# indication_panel.net
KiCad netlist of a schematic drawn in EAGLE
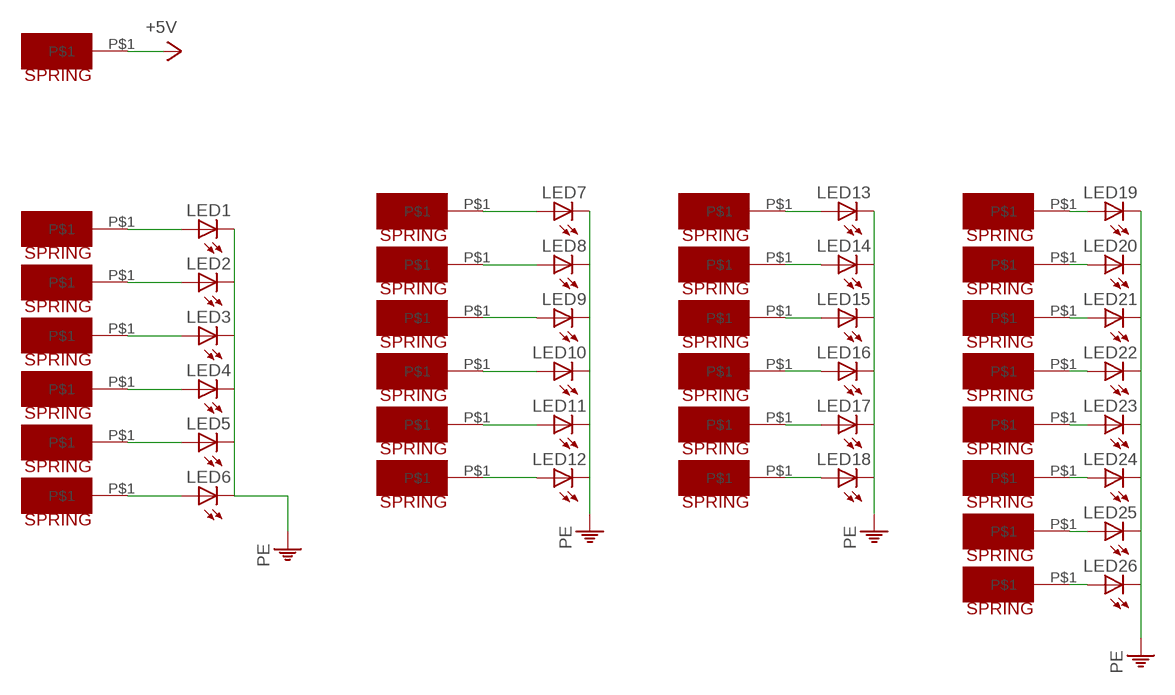
[diagram p0: schematic, sheet 1]

(export (version "E")
  (design (tool "Eeschema 10.0.6"))
  (components
    (comp (ref "+5V")
      (value "SPRING")
      (footprint "eagle-import:SPRING")
      (libsource (lib "eagle-import") (part "SPRING"))
    )
    (comp (ref "LED1")
      (value "LEDCHIPLED_0805")
      (footprint "eagle-import:CHIPLED_0805")
      (libsource (lib "eagle-import") (part "LEDCHIPLED_0805"))
    )
    (comp (ref "LED2")
      (value "LEDCHIPLED_0805")
      (footprint "eagle-import:CHIPLED_0805")
      (libsource (lib "eagle-import") (part "LEDCHIPLED_0805"))
    )
    (comp (ref "LED3")
      (value "LEDCHIPLED_0805")
      (footprint "eagle-import:CHIPLED_0805")
      (libsource (lib "eagle-import") (part "LEDCHIPLED_0805"))
    )
    (comp (ref "LED4")
      (value "LEDCHIPLED_0805")
      (footprint "eagle-import:CHIPLED_0805")
      (libsource (lib "eagle-import") (part "LEDCHIPLED_0805"))
    )
    (comp (ref "LED5")
      (value "LEDCHIPLED_0805")
      (footprint "eagle-import:CHIPLED_0805")
      (libsource (lib "eagle-import") (part "LEDCHIPLED_0805"))
    )
    (comp (ref "LED6")
      (value "LEDCHIPLED_0805")
      (footprint "eagle-import:CHIPLED_0805")
      (libsource (lib "eagle-import") (part "LEDCHIPLED_0805"))
    )
    (comp (ref "LED7")
      (value "LEDCHIPLED_0805")
      (footprint "eagle-import:CHIPLED_0805")
      (libsource (lib "eagle-import") (part "LEDCHIPLED_0805"))
    )
    (comp (ref "LED8")
      (value "LEDCHIPLED_0805")
      (footprint "eagle-import:CHIPLED_0805")
      (libsource (lib "eagle-import") (part "LEDCHIPLED_0805"))
    )
    (comp (ref "LED9")
      (value "LEDCHIPLED_0805")
      (footprint "eagle-import:CHIPLED_0805")
      (libsource (lib "eagle-import") (part "LEDCHIPLED_0805"))
    )
    (comp (ref "LED10")
      (value "LEDCHIPLED_0805")
      (footprint "eagle-import:CHIPLED_0805")
      (libsource (lib "eagle-import") (part "LEDCHIPLED_0805"))
    )
    (comp (ref "LED11")
      (value "LEDCHIPLED_0805")
      (footprint "eagle-import:CHIPLED_0805")
      (libsource (lib "eagle-import") (part "LEDCHIPLED_0805"))
    )
    (comp (ref "LED12")
      (value "LEDCHIPLED_0805")
      (footprint "eagle-import:CHIPLED_0805")
      (libsource (lib "eagle-import") (part "LEDCHIPLED_0805"))
    )
    (comp (ref "LED13")
      (value "LEDCHIPLED_0805")
      (footprint "eagle-import:CHIPLED_0805")
      (libsource (lib "eagle-import") (part "LEDCHIPLED_0805"))
    )
    (comp (ref "LED14")
      (value "LEDCHIPLED_0805")
      (footprint "eagle-import:CHIPLED_0805")
      (libsource (lib "eagle-import") (part "LEDCHIPLED_0805"))
    )
    (comp (ref "LED15")
      (value "LEDCHIPLED_0805")
      (footprint "eagle-import:CHIPLED_0805")
      (libsource (lib "eagle-import") (part "LEDCHIPLED_0805"))
    )
    (comp (ref "LED16")
      (value "LEDCHIPLED_0805")
      (footprint "eagle-import:CHIPLED_0805")
      (libsource (lib "eagle-import") (part "LEDCHIPLED_0805"))
    )
    (comp (ref "LED17")
      (value "LEDCHIPLED_0805")
      (footprint "eagle-import:CHIPLED_0805")
      (libsource (lib "eagle-import") (part "LEDCHIPLED_0805"))
    )
    (comp (ref "LED18")
      (value "LEDCHIPLED_0805")
      (footprint "eagle-import:CHIPLED_0805")
      (libsource (lib "eagle-import") (part "LEDCHIPLED_0805"))
    )
    (comp (ref "LED19")
      (value "LEDCHIPLED_0805")
      (footprint "eagle-import:CHIPLED_0805")
      (libsource (lib "eagle-import") (part "LEDCHIPLED_0805"))
    )
    (comp (ref "LED20")
      (value "LEDCHIPLED_0805")
      (footprint "eagle-import:CHIPLED_0805")
      (libsource (lib "eagle-import") (part "LEDCHIPLED_0805"))
    )
    (comp (ref "LED21")
      (value "LEDCHIPLED_0805")
      (footprint "eagle-import:CHIPLED_0805")
      (libsource (lib "eagle-import") (part "LEDCHIPLED_0805"))
    )
    (comp (ref "LED22")
      (value "LEDCHIPLED_0805")
      (footprint "eagle-import:CHIPLED_0805")
      (libsource (lib "eagle-import") (part "LEDCHIPLED_0805"))
    )
    (comp (ref "LED23")
      (value "LEDCHIPLED_0805")
      (footprint "eagle-import:CHIPLED_0805")
      (libsource (lib "eagle-import") (part "LEDCHIPLED_0805"))
    )
    (comp (ref "LED24")
      (value "LEDCHIPLED_0805")
      (footprint "eagle-import:CHIPLED_0805")
      (libsource (lib "eagle-import") (part "LEDCHIPLED_0805"))
    )
    (comp (ref "LED25")
      (value "LEDCHIPLED_0805")
      (footprint "eagle-import:CHIPLED_0805")
      (libsource (lib "eagle-import") (part "LEDCHIPLED_0805"))
    )
    (comp (ref "LED26")
      (value "LEDCHIPLED_0805")
      (footprint "eagle-import:CHIPLED_0805")
      (libsource (lib "eagle-import") (part "LEDCHIPLED_0805"))
    )
    (comp (ref "U$1")
      (value "SPRING")
      (footprint "eagle-import:SPRING")
      (libsource (lib "eagle-import") (part "SPRING"))
    )
    (comp (ref "U$2")
      (value "SPRING")
      (footprint "eagle-import:SPRING")
      (libsource (lib "eagle-import") (part "SPRING"))
    )
    (comp (ref "U$3")
      (value "SPRING")
      (footprint "eagle-import:SPRING")
      (libsource (lib "eagle-import") (part "SPRING"))
    )
    (comp (ref "U$4")
      (value "SPRING")
      (footprint "eagle-import:SPRING")
      (libsource (lib "eagle-import") (part "SPRING"))
    )
    (comp (ref "U$6")
      (value "SPRING")
      (footprint "eagle-import:SPRING")
      (libsource (lib "eagle-import") (part "SPRING"))
    )
    (comp (ref "U$7")
      (value "SPRING")
      (footprint "eagle-import:SPRING")
      (libsource (lib "eagle-import") (part "SPRING"))
    )
    (comp (ref "U$8")
      (value "SPRING")
      (footprint "eagle-import:SPRING")
      (libsource (lib "eagle-import") (part "SPRING"))
    )
    (comp (ref "U$9")
      (value "SPRING")
      (footprint "eagle-import:SPRING")
      (libsource (lib "eagle-import") (part "SPRING"))
    )
    (comp (ref "U$10")
      (value "SPRING")
      (footprint "eagle-import:SPRING")
      (libsource (lib "eagle-import") (part "SPRING"))
    )
    (comp (ref "U$11")
      (value "SPRING")
      (footprint "eagle-import:SPRING")
      (libsource (lib "eagle-import") (part "SPRING"))
    )
    (comp (ref "U$12")
      (value "SPRING")
      (footprint "eagle-import:SPRING")
      (libsource (lib "eagle-import") (part "SPRING"))
    )
    (comp (ref "U$13")
      (value "SPRING")
      (footprint "eagle-import:SPRING")
      (libsource (lib "eagle-import") (part "SPRING"))
    )
    (comp (ref "U$14")
      (value "SPRING")
      (footprint "eagle-import:SPRING")
      (libsource (lib "eagle-import") (part "SPRING"))
    )
    (comp (ref "U$15")
      (value "SPRING")
      (footprint "eagle-import:SPRING")
      (libsource (lib "eagle-import") (part "SPRING"))
    )
    (comp (ref "U$16")
      (value "SPRING")
      (footprint "eagle-import:SPRING")
      (libsource (lib "eagle-import") (part "SPRING"))
    )
    (comp (ref "U$17")
      (value "SPRING")
      (footprint "eagle-import:SPRING")
      (libsource (lib "eagle-import") (part "SPRING"))
    )
    (comp (ref "U$18")
      (value "SPRING")
      (footprint "eagle-import:SPRING")
      (libsource (lib "eagle-import") (part "SPRING"))
    )
    (comp (ref "U$19")
      (value "SPRING")
      (footprint "eagle-import:SPRING")
      (libsource (lib "eagle-import") (part "SPRING"))
    )
    (comp (ref "U$20")
      (value "SPRING")
      (footprint "eagle-import:SPRING")
      (libsource (lib "eagle-import") (part "SPRING"))
    )
    (comp (ref "U$21")
      (value "SPRING")
      (footprint "eagle-import:SPRING")
      (libsource (lib "eagle-import") (part "SPRING"))
    )
    (comp (ref "U$22")
      (value "SPRING")
      (footprint "eagle-import:SPRING")
      (libsource (lib "eagle-import") (part "SPRING"))
    )
    (comp (ref "U$23")
      (value "SPRING")
      (footprint "eagle-import:SPRING")
      (libsource (lib "eagle-import") (part "SPRING"))
    )
    (comp (ref "U$24")
      (value "SPRING")
      (footprint "eagle-import:SPRING")
      (libsource (lib "eagle-import") (part "SPRING"))
    )
    (comp (ref "U$25")
      (value "SPRING")
      (footprint "eagle-import:SPRING")
      (libsource (lib "eagle-import") (part "SPRING"))
    )
    (comp (ref "U$26")
      (value "SPRING")
      (footprint "eagle-import:SPRING")
      (libsource (lib "eagle-import") (part "SPRING"))
    )
    (comp (ref "U$27")
      (value "SPRING")
      (footprint "eagle-import:SPRING")
      (libsource (lib "eagle-import") (part "SPRING"))
    )
  )
  (nets
    (net (code "1") (name "+5V") (class "Default")
      (node (ref "U$27") (pin "P$1") (pinfunction "P$1_P$1") (pintype "bidirectional"))
    )
    (net (code "2") (name "Net-(+5V-PadP$1)") (class "Default")
      (node (ref "+5V") (pin "P$1") (pinfunction "P$1_P$1") (pintype "bidirectional"))
      (node (ref "LED5") (pin "A") (pinfunction "A_A") (pintype "passive"))
    )
    (net (code "3") (name "Net-(LED1-PadA)") (class "Default")
      (node (ref "LED1") (pin "A") (pinfunction "A_A") (pintype "passive"))
      (node (ref "U$1") (pin "P$1") (pinfunction "P$1_P$1") (pintype "bidirectional"))
    )
    (net (code "4") (name "Net-(LED2-PadA)") (class "Default")
      (node (ref "LED2") (pin "A") (pinfunction "A_A") (pintype "passive"))
      (node (ref "U$2") (pin "P$1") (pinfunction "P$1_P$1") (pintype "bidirectional"))
    )
    (net (code "5") (name "Net-(LED3-PadA)") (class "Default")
      (node (ref "LED3") (pin "A") (pinfunction "A_A") (pintype "passive"))
      (node (ref "U$3") (pin "P$1") (pinfunction "P$1_P$1") (pintype "bidirectional"))
    )
    (net (code "6") (name "Net-(LED4-PadA)") (class "Default")
      (node (ref "LED4") (pin "A") (pinfunction "A_A") (pintype "passive"))
      (node (ref "U$4") (pin "P$1") (pinfunction "P$1_P$1") (pintype "bidirectional"))
    )
    (net (code "7") (name "Net-(LED6-PadA)") (class "Default")
      (node (ref "LED6") (pin "A") (pinfunction "A_A") (pintype "passive"))
      (node (ref "U$6") (pin "P$1") (pinfunction "P$1_P$1") (pintype "bidirectional"))
    )
    (net (code "8") (name "Net-(LED7-PadA)") (class "Default")
      (node (ref "LED7") (pin "A") (pinfunction "A_A") (pintype "passive"))
      (node (ref "U$7") (pin "P$1") (pinfunction "P$1_P$1") (pintype "bidirectional"))
    )
    (net (code "9") (name "Net-(LED8-PadA)") (class "Default")
      (node (ref "LED8") (pin "A") (pinfunction "A_A") (pintype "passive"))
      (node (ref "U$8") (pin "P$1") (pinfunction "P$1_P$1") (pintype "bidirectional"))
    )
    (net (code "10") (name "Net-(LED9-PadA)") (class "Default")
      (node (ref "LED9") (pin "A") (pinfunction "A_A") (pintype "passive"))
      (node (ref "U$9") (pin "P$1") (pinfunction "P$1_P$1") (pintype "bidirectional"))
    )
    (net (code "11") (name "Net-(LED10-PadA)") (class "Default")
      (node (ref "LED10") (pin "A") (pinfunction "A_A") (pintype "passive"))
      (node (ref "U$10") (pin "P$1") (pinfunction "P$1_P$1") (pintype "bidirectional"))
    )
    (net (code "12") (name "Net-(LED11-PadA)") (class "Default")
      (node (ref "LED11") (pin "A") (pinfunction "A_A") (pintype "passive"))
      (node (ref "U$11") (pin "P$1") (pinfunction "P$1_P$1") (pintype "bidirectional"))
    )
    (net (code "13") (name "Net-(LED12-PadA)") (class "Default")
      (node (ref "LED12") (pin "A") (pinfunction "A_A") (pintype "passive"))
      (node (ref "U$12") (pin "P$1") (pinfunction "P$1_P$1") (pintype "bidirectional"))
    )
    (net (code "14") (name "Net-(LED13-PadA)") (class "Default")
      (node (ref "LED13") (pin "A") (pinfunction "A_A") (pintype "passive"))
      (node (ref "U$19") (pin "P$1") (pinfunction "P$1_P$1") (pintype "bidirectional"))
    )
    (net (code "15") (name "Net-(LED14-PadA)") (class "Default")
      (node (ref "LED14") (pin "A") (pinfunction "A_A") (pintype "passive"))
      (node (ref "U$20") (pin "P$1") (pinfunction "P$1_P$1") (pintype "bidirectional"))
    )
    (net (code "16") (name "Net-(LED15-PadA)") (class "Default")
      (node (ref "LED15") (pin "A") (pinfunction "A_A") (pintype "passive"))
      (node (ref "U$21") (pin "P$1") (pinfunction "P$1_P$1") (pintype "bidirectional"))
    )
    (net (code "17") (name "Net-(LED16-PadA)") (class "Default")
      (node (ref "LED16") (pin "A") (pinfunction "A_A") (pintype "passive"))
      (node (ref "U$22") (pin "P$1") (pinfunction "P$1_P$1") (pintype "bidirectional"))
    )
    (net (code "18") (name "Net-(LED17-PadA)") (class "Default")
      (node (ref "LED17") (pin "A") (pinfunction "A_A") (pintype "passive"))
      (node (ref "U$23") (pin "P$1") (pinfunction "P$1_P$1") (pintype "bidirectional"))
    )
    (net (code "19") (name "Net-(LED18-PadA)") (class "Default")
      (node (ref "LED18") (pin "A") (pinfunction "A_A") (pintype "passive"))
      (node (ref "U$24") (pin "P$1") (pinfunction "P$1_P$1") (pintype "bidirectional"))
    )
    (net (code "20") (name "Net-(LED19-PadA)") (class "Default")
      (node (ref "LED19") (pin "A") (pinfunction "A_A") (pintype "passive"))
      (node (ref "U$13") (pin "P$1") (pinfunction "P$1_P$1") (pintype "bidirectional"))
    )
    (net (code "21") (name "Net-(LED20-PadA)") (class "Default")
      (node (ref "LED20") (pin "A") (pinfunction "A_A") (pintype "passive"))
      (node (ref "U$14") (pin "P$1") (pinfunction "P$1_P$1") (pintype "bidirectional"))
    )
    (net (code "22") (name "Net-(LED21-PadA)") (class "Default")
      (node (ref "LED21") (pin "A") (pinfunction "A_A") (pintype "passive"))
      (node (ref "U$15") (pin "P$1") (pinfunction "P$1_P$1") (pintype "bidirectional"))
    )
    (net (code "23") (name "Net-(LED22-PadA)") (class "Default")
      (node (ref "LED22") (pin "A") (pinfunction "A_A") (pintype "passive"))
      (node (ref "U$16") (pin "P$1") (pinfunction "P$1_P$1") (pintype "bidirectional"))
    )
    (net (code "24") (name "Net-(LED23-PadA)") (class "Default")
      (node (ref "LED23") (pin "A") (pinfunction "A_A") (pintype "passive"))
      (node (ref "U$17") (pin "P$1") (pinfunction "P$1_P$1") (pintype "bidirectional"))
    )
    (net (code "25") (name "Net-(LED24-PadA)") (class "Default")
      (node (ref "LED24") (pin "A") (pinfunction "A_A") (pintype "passive"))
      (node (ref "U$18") (pin "P$1") (pinfunction "P$1_P$1") (pintype "bidirectional"))
    )
    (net (code "26") (name "Net-(LED25-PadA)") (class "Default")
      (node (ref "LED25") (pin "A") (pinfunction "A_A") (pintype "passive"))
      (node (ref "U$25") (pin "P$1") (pinfunction "P$1_P$1") (pintype "bidirectional"))
    )
    (net (code "27") (name "Net-(LED26-PadA)") (class "Default")
      (node (ref "LED26") (pin "A") (pinfunction "A_A") (pintype "passive"))
      (node (ref "U$26") (pin "P$1") (pinfunction "P$1_P$1") (pintype "bidirectional"))
    )
    (net (code "28") (name "PE") (class "Default")
      (node (ref "LED1") (pin "C") (pinfunction "C_C") (pintype "passive"))
      (node (ref "LED10") (pin "C") (pinfunction "C_C") (pintype "passive"))
      (node (ref "LED11") (pin "C") (pinfunction "C_C") (pintype "passive"))
      (node (ref "LED12") (pin "C") (pinfunction "C_C") (pintype "passive"))
      (node (ref "LED13") (pin "C") (pinfunction "C_C") (pintype "passive"))
      (node (ref "LED14") (pin "C") (pinfunction "C_C") (pintype "passive"))
      (node (ref "LED15") (pin "C") (pinfunction "C_C") (pintype "passive"))
      (node (ref "LED16") (pin "C") (pinfunction "C_C") (pintype "passive"))
      (node (ref "LED17") (pin "C") (pinfunction "C_C") (pintype "passive"))
      (node (ref "LED18") (pin "C") (pinfunction "C_C") (pintype "passive"))
      (node (ref "LED19") (pin "C") (pinfunction "C_C") (pintype "passive"))
      (node (ref "LED2") (pin "C") (pinfunction "C_C") (pintype "passive"))
      (node (ref "LED20") (pin "C") (pinfunction "C_C") (pintype "passive"))
      (node (ref "LED21") (pin "C") (pinfunction "C_C") (pintype "passive"))
      (node (ref "LED22") (pin "C") (pinfunction "C_C") (pintype "passive"))
      (node (ref "LED23") (pin "C") (pinfunction "C_C") (pintype "passive"))
      (node (ref "LED24") (pin "C") (pinfunction "C_C") (pintype "passive"))
      (node (ref "LED25") (pin "C") (pinfunction "C_C") (pintype "passive"))
      (node (ref "LED26") (pin "C") (pinfunction "C_C") (pintype "passive"))
      (node (ref "LED3") (pin "C") (pinfunction "C_C") (pintype "passive"))
      (node (ref "LED4") (pin "C") (pinfunction "C_C") (pintype "passive"))
      (node (ref "LED5") (pin "C") (pinfunction "C_C") (pintype "passive"))
      (node (ref "LED6") (pin "C") (pinfunction "C_C") (pintype "passive"))
      (node (ref "LED7") (pin "C") (pinfunction "C_C") (pintype "passive"))
      (node (ref "LED8") (pin "C") (pinfunction "C_C") (pintype "passive"))
      (node (ref "LED9") (pin "C") (pinfunction "C_C") (pintype "passive"))
    )
  )
)
